# 20dB_Attenuator_RX.net
KiCad netlist of a schematic drawn in Altium Designer
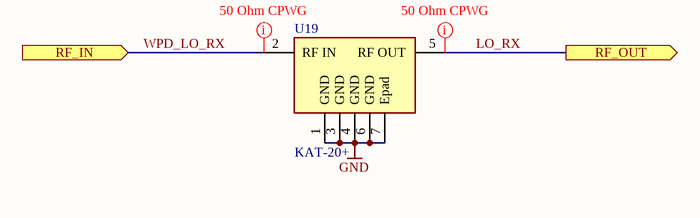
[diagram p0: 20dB_Attenuator_RX.SchDoc]

(export (version "E")
  (design (tool "Eeschema 10.0.6"))
  (components
    (comp (ref "U19")
      (value "KAT-20+")
      (footprint "MC1630-1")
      (fields (field (name "MANUFACTURER") "Minicircuits"))
      (libsource (lib "database_library") (part "KAT-XX+"))
    )
  )
  (nets
    (net (code "1") (name "/LO_RX") (class "Default")
      (node (ref "U19") (pin "5") (pinfunction "RF_OUT_5") (pintype "passive"))
    )
    (net (code "2") (name "/WPD_LO_RX") (class "Default")
      (node (ref "U19") (pin "2") (pinfunction "RF_IN_2") (pintype "passive"))
    )
    (net (code "3") (name "GND") (class "Default")
      (node (ref "U19") (pin "1") (pinfunction "GND_1") (pintype "passive"))
      (node (ref "U19") (pin "3") (pinfunction "GND_3") (pintype "passive"))
      (node (ref "U19") (pin "4") (pinfunction "GND_4") (pintype "passive"))
      (node (ref "U19") (pin "6") (pinfunction "GND_6") (pintype "passive"))
      (node (ref "U19") (pin "7") (pinfunction "Epad_7") (pintype "passive"))
    )
  )
)
